# helmet_blinker_light_v0_2.net
KiCad netlist of a schematic drawn in EAGLE
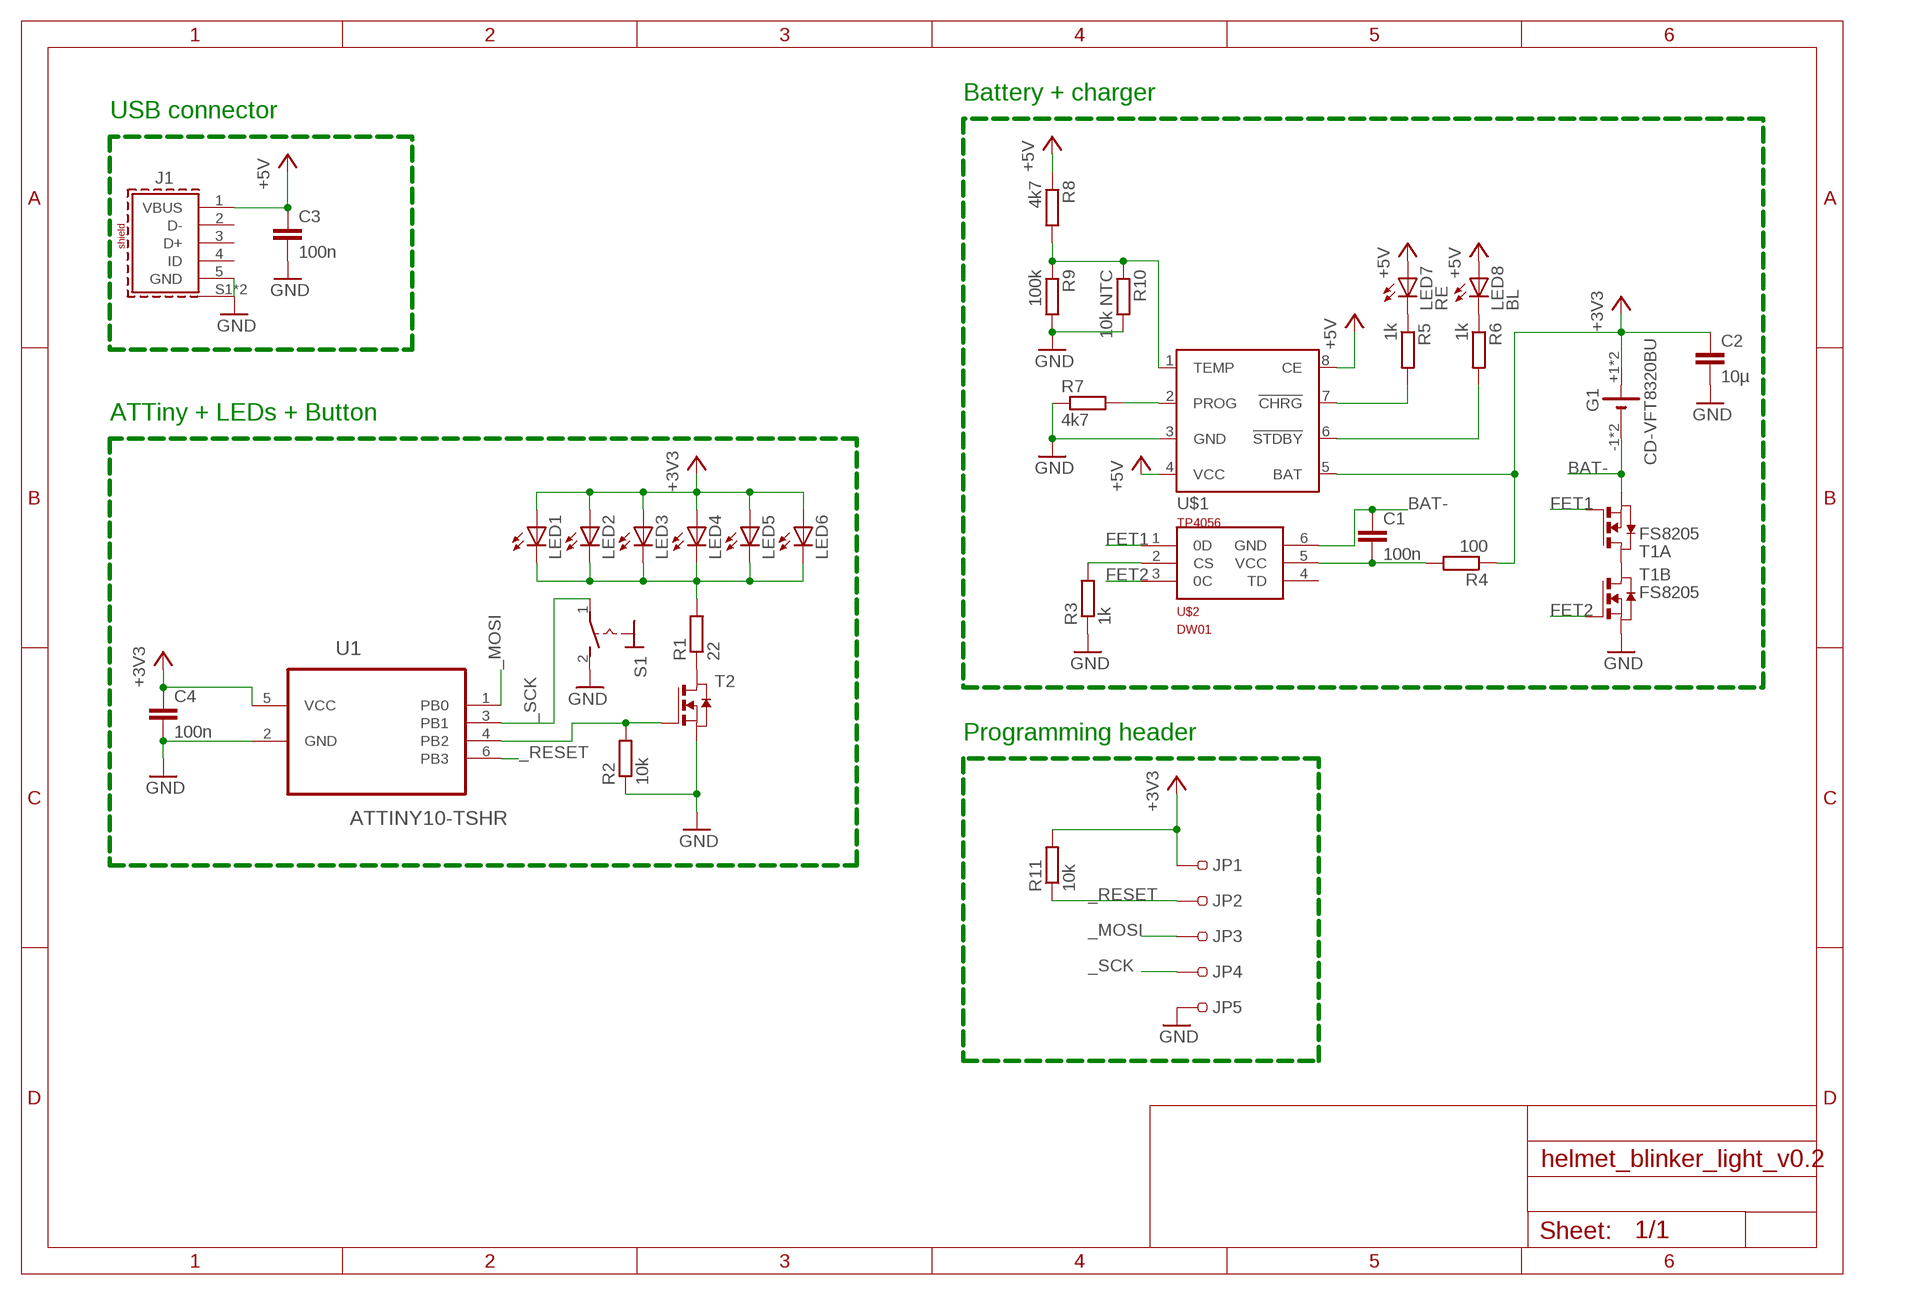
[diagram p0: schematic, sheet 1]

(export (version "E")
  (design (tool "Eeschema 10.0.6"))
  (components
    (comp (ref "C1")
      (value "100n")
      (footprint "eagle-import:C0402K")
      (libsource (lib "eagle-import") (part "C-EUC0402K"))
    )
    (comp (ref "C2")
      (value "10µ")
      (footprint "eagle-import:C0805K")
      (libsource (lib "eagle-import") (part "C-EUC0805K"))
    )
    (comp (ref "C3")
      (value "100n")
      (footprint "eagle-import:C0402K")
      (libsource (lib "eagle-import") (part "C-EUC0402K"))
    )
    (comp (ref "C4")
      (value "100n")
      (footprint "eagle-import:C0402K")
      (libsource (lib "eagle-import") (part "C-EUC0402K"))
    )
    (comp (ref "G1")
      (value "CD-VFT8320BU")
      (footprint "eagle-import:CS-VFT8320BU")
      (libsource (lib "eagle-import") (part "CD-VFT8320BU"))
    )
    (comp (ref "J1")
      (value "614105150621")
      (footprint "eagle-import:614105150621")
      (libsource (lib "eagle-import") (part "614105150621"))
    )
    (comp (ref "JP1")
      (value "0.7MM_POGO-PINS")
      (footprint "eagle-import:0.7MM_POGO-PINS")
      (libsource (lib "eagle-import") (part "0.7MM_POGO-PINS"))
    )
    (comp (ref "JP2")
      (value "0.7MM_POGO-PINS")
      (footprint "eagle-import:0.7MM_POGO-PINS")
      (libsource (lib "eagle-import") (part "0.7MM_POGO-PINS"))
    )
    (comp (ref "JP3")
      (value "0.7MM_POGO-PINS")
      (footprint "eagle-import:0.7MM_POGO-PINS")
      (libsource (lib "eagle-import") (part "0.7MM_POGO-PINS"))
    )
    (comp (ref "JP4")
      (value "0.7MM_POGO-PINS")
      (footprint "eagle-import:0.7MM_POGO-PINS")
      (libsource (lib "eagle-import") (part "0.7MM_POGO-PINS"))
    )
    (comp (ref "JP5")
      (value "0.7MM_POGO-PINS")
      (footprint "eagle-import:0.7MM_POGO-PINS")
      (libsource (lib "eagle-import") (part "0.7MM_POGO-PINS"))
    )
    (comp (ref "LED1")
      (value "LEDCHIPLED_0805")
      (footprint "eagle-import:CHIPLED_0805")
      (libsource (lib "eagle-import") (part "LEDCHIPLED_0805"))
    )
    (comp (ref "LED2")
      (value "LEDCHIPLED_0805")
      (footprint "eagle-import:CHIPLED_0805")
      (libsource (lib "eagle-import") (part "LEDCHIPLED_0805"))
    )
    (comp (ref "LED3")
      (value "LEDCHIPLED_0805")
      (footprint "eagle-import:CHIPLED_0805")
      (libsource (lib "eagle-import") (part "LEDCHIPLED_0805"))
    )
    (comp (ref "LED4")
      (value "LEDCHIPLED_0805")
      (footprint "eagle-import:CHIPLED_0805")
      (libsource (lib "eagle-import") (part "LEDCHIPLED_0805"))
    )
    (comp (ref "LED5")
      (value "LEDCHIPLED_0805")
      (footprint "eagle-import:CHIPLED_0805")
      (libsource (lib "eagle-import") (part "LEDCHIPLED_0805"))
    )
    (comp (ref "LED6")
      (value "LEDCHIPLED_0805")
      (footprint "eagle-import:CHIPLED_0805")
      (libsource (lib "eagle-import") (part "LEDCHIPLED_0805"))
    )
    (comp (ref "LED7")
      (value "RE")
      (footprint "eagle-import:CHIPLED_0805")
      (libsource (lib "eagle-import") (part "LEDCHIPLED_0805"))
    )
    (comp (ref "LED8")
      (value "BL")
      (footprint "eagle-import:CHIPLED_0805")
      (libsource (lib "eagle-import") (part "LEDCHIPLED_0805"))
    )
    (comp (ref "R1")
      (value "22")
      (footprint "eagle-import:R0805")
      (libsource (lib "eagle-import") (part "R-EU_R0805"))
    )
    (comp (ref "R2")
      (value "10k")
      (footprint "eagle-import:R0402")
      (libsource (lib "eagle-import") (part "R-EU_R0402"))
    )
    (comp (ref "R3")
      (value "1k")
      (footprint "eagle-import:R0402")
      (libsource (lib "eagle-import") (part "R-EU_R0402"))
    )
    (comp (ref "R4")
      (value "100")
      (footprint "eagle-import:R0402")
      (libsource (lib "eagle-import") (part "R-EU_R0402"))
    )
    (comp (ref "R5")
      (value "1k")
      (footprint "eagle-import:R0402")
      (libsource (lib "eagle-import") (part "R-EU_R0402"))
    )
    (comp (ref "R6")
      (value "1k")
      (footprint "eagle-import:R0402")
      (libsource (lib "eagle-import") (part "R-EU_R0402"))
    )
    (comp (ref "R7")
      (value "4k7")
      (footprint "eagle-import:R0402")
      (libsource (lib "eagle-import") (part "R-EU_R0402"))
    )
    (comp (ref "R8")
      (value "4k7")
      (footprint "eagle-import:R0402")
      (libsource (lib "eagle-import") (part "R-EU_R0402"))
    )
    (comp (ref "R9")
      (value "100k")
      (footprint "eagle-import:R0402")
      (libsource (lib "eagle-import") (part "R-EU_R0402"))
    )
    (comp (ref "R10")
      (value "10k NTC")
      (footprint "eagle-import:R0805")
      (libsource (lib "eagle-import") (part "R-EU_R0805"))
    )
    (comp (ref "R11")
      (value "10k")
      (footprint "eagle-import:R0402")
      (libsource (lib "eagle-import") (part "R-EU_R0402"))
    )
    (comp (ref "S1")
      (value "TS-1088")
      (footprint "eagle-import:TS-1088")
      (libsource (lib "eagle-import") (part "TS-1088"))
    )
    (comp (ref "T1")
      (value "FS8205")
      (footprint "eagle-import:TSSOP-8")
      (libsource (lib "eagle-import") (part "DMN3024LSD"))
    )
    (comp (ref "T2")
      (value "NMOSSOT23")
      (footprint "eagle-import:SOT-23")
      (libsource (lib "eagle-import") (part "NMOSSOT23"))
    )
    (comp (ref "U$1")
      (value "TP4056")
      (footprint "eagle-import:SOT23-8")
      (libsource (lib "eagle-import") (part "TP4056"))
    )
    (comp (ref "U$2")
      (value "DW01")
      (footprint "eagle-import:SOT23-6")
      (libsource (lib "eagle-import") (part "DW01"))
    )
    (comp (ref "U1")
      (value "ATTINY10-TSHR")
      (footprint "eagle-import:SOT95P280X145-6N")
      (libsource (lib "eagle-import") (part "ATTINY10-TSHR"))
    )
  )
  (nets
    (net (code "1") (name "+3V3") (class "Default")
      (node (ref "C2") (pin "1") (pinfunction "1_1") (pintype "passive"))
      (node (ref "C4") (pin "1") (pinfunction "1_1") (pintype "passive"))
      (node (ref "G1") (pin "+1") (pinfunction "+_+1") (pintype "passive"))
      (node (ref "G1") (pin "+2") (pinfunction "+_+2") (pintype "passive"))
      (node (ref "JP1") (pin "1") (pinfunction "1_1") (pintype "passive"))
      (node (ref "LED1") (pin "A") (pinfunction "A_A") (pintype "passive"))
      (node (ref "LED2") (pin "A") (pinfunction "A_A") (pintype "passive"))
      (node (ref "LED3") (pin "A") (pinfunction "A_A") (pintype "passive"))
      (node (ref "LED4") (pin "A") (pinfunction "A_A") (pintype "passive"))
      (node (ref "LED5") (pin "A") (pinfunction "A_A") (pintype "passive"))
      (node (ref "LED6") (pin "A") (pinfunction "A_A") (pintype "passive"))
      (node (ref "R11") (pin "2") (pinfunction "2_2") (pintype "passive"))
      (node (ref "R4") (pin "1") (pinfunction "1_1") (pintype "passive"))
      (node (ref "U$1") (pin "5") (pinfunction "BAT_5") (pintype "bidirectional"))
      (node (ref "U1") (pin "5") (pinfunction "VCC_5") (pintype "power_in"))
    )
    (net (code "2") (name "+5V") (class "Default")
      (node (ref "C3") (pin "1") (pinfunction "1_1") (pintype "passive"))
      (node (ref "J1") (pin "1") (pinfunction "VBUS_1") (pintype "passive"))
      (node (ref "LED7") (pin "A") (pinfunction "A_A") (pintype "passive"))
      (node (ref "LED8") (pin "A") (pinfunction "A_A") (pintype "passive"))
      (node (ref "R8") (pin "1") (pinfunction "1_1") (pintype "passive"))
      (node (ref "U$1") (pin "4") (pinfunction "VCC_4") (pintype "bidirectional"))
      (node (ref "U$1") (pin "8") (pinfunction "CE_8") (pintype "bidirectional"))
    )
    (net (code "3") (name "/BAT-") (class "Default")
      (node (ref "C1") (pin "1") (pinfunction "1_1") (pintype "passive"))
      (node (ref "G1") (pin "-1") (pinfunction "-_-1") (pintype "passive"))
      (node (ref "G1") (pin "-2") (pinfunction "-_-2") (pintype "passive"))
      (node (ref "T1") (pin "2") (pinfunction "S_2") (pintype "passive"))
      (node (ref "T1") (pin "3") (pinfunction "S_3") (pintype "passive"))
      (node (ref "U$2") (pin "6") (pinfunction "GND_6") (pintype "bidirectional"))
    )
    (net (code "4") (name "/FET1") (class "Default")
      (node (ref "T1") (pin "4") (pinfunction "G_4") (pintype "passive"))
      (node (ref "U$2") (pin "1") (pinfunction "0D_1") (pintype "bidirectional"))
    )
    (net (code "5") (name "/FET2") (class "Default")
      (node (ref "T1") (pin "5") (pinfunction "G_5") (pintype "passive"))
      (node (ref "U$2") (pin "3") (pinfunction "0C_3") (pintype "bidirectional"))
    )
    (net (code "6") (name "/_MOSI") (class "Default")
      (node (ref "JP3") (pin "1") (pinfunction "1_1") (pintype "passive"))
      (node (ref "U1") (pin "1") (pinfunction "PB0_1") (pintype "bidirectional"))
    )
    (net (code "7") (name "/_RESET") (class "Default")
      (node (ref "JP2") (pin "1") (pinfunction "1_1") (pintype "passive"))
      (node (ref "R11") (pin "1") (pinfunction "1_1") (pintype "passive"))
      (node (ref "U1") (pin "6") (pinfunction "PB3_6") (pintype "bidirectional"))
    )
    (net (code "8") (name "/_SCK") (class "Default")
      (node (ref "JP4") (pin "1") (pinfunction "1_1") (pintype "passive"))
      (node (ref "S1") (pin "1") (pinfunction "P_1") (pintype "passive"))
      (node (ref "U1") (pin "3") (pinfunction "PB1_3") (pintype "bidirectional"))
    )
    (net (code "9") (name "GND") (class "Default")
      (node (ref "C2") (pin "2") (pinfunction "2_2") (pintype "passive"))
      (node (ref "C3") (pin "2") (pinfunction "2_2") (pintype "passive"))
      (node (ref "C4") (pin "2") (pinfunction "2_2") (pintype "passive"))
      (node (ref "J1") (pin "5") (pinfunction "GND_5") (pintype "passive"))
      (node (ref "J1") (pin "S1") (pinfunction "SHIELD_S1") (pintype "passive"))
      (node (ref "J1") (pin "S2") (pinfunction "SHIELD_S2") (pintype "passive"))
      (node (ref "JP5") (pin "1") (pinfunction "1_1") (pintype "passive"))
      (node (ref "R10") (pin "2") (pinfunction "2_2") (pintype "passive"))
      (node (ref "R2") (pin "1") (pinfunction "1_1") (pintype "passive"))
      (node (ref "R3") (pin "1") (pinfunction "1_1") (pintype "passive"))
      (node (ref "R7") (pin "1") (pinfunction "1_1") (pintype "passive"))
      (node (ref "R9") (pin "2") (pinfunction "2_2") (pintype "passive"))
      (node (ref "S1") (pin "2") (pinfunction "S_2") (pintype "passive"))
      (node (ref "T1") (pin "6") (pinfunction "S_6") (pintype "passive"))
      (node (ref "T1") (pin "7") (pinfunction "S_7") (pintype "passive"))
      (node (ref "T2") (pin "2") (pinfunction "S_2") (pintype "passive"))
      (node (ref "U$1") (pin "3") (pinfunction "GND_3") (pintype "bidirectional"))
      (node (ref "U1") (pin "2") (pinfunction "GND_2") (pintype "passive"))
    )
    (net (code "10") (name "Net-(LED1-PadC)") (class "Default")
      (node (ref "LED1") (pin "C") (pinfunction "C_C") (pintype "passive"))
      (node (ref "LED2") (pin "C") (pinfunction "C_C") (pintype "passive"))
      (node (ref "LED3") (pin "C") (pinfunction "C_C") (pintype "passive"))
      (node (ref "LED4") (pin "C") (pinfunction "C_C") (pintype "passive"))
      (node (ref "LED5") (pin "C") (pinfunction "C_C") (pintype "passive"))
      (node (ref "LED6") (pin "C") (pinfunction "C_C") (pintype "passive"))
      (node (ref "R1") (pin "2") (pinfunction "2_2") (pintype "passive"))
    )
    (net (code "11") (name "Net-(LED7-PadC)") (class "Default")
      (node (ref "LED7") (pin "C") (pinfunction "C_C") (pintype "passive"))
      (node (ref "R5") (pin "1") (pinfunction "1_1") (pintype "passive"))
    )
    (net (code "12") (name "Net-(LED8-PadC)") (class "Default")
      (node (ref "LED8") (pin "C") (pinfunction "C_C") (pintype "passive"))
      (node (ref "R6") (pin "1") (pinfunction "1_1") (pintype "passive"))
    )
    (net (code "13") (name "Net-(T1A-D)") (class "Default")
      (node (ref "T1") (pin "1") (pinfunction "D_1") (pintype "passive"))
      (node (ref "T1") (pin "8") (pinfunction "D_8") (pintype "passive"))
    )
    (net (code "14") (name "Net-(T2-D)") (class "Default")
      (node (ref "R1") (pin "1") (pinfunction "1_1") (pintype "passive"))
      (node (ref "T2") (pin "1") (pinfunction "D_1") (pintype "passive"))
    )
    (net (code "15") (name "Net-(T2-G)") (class "Default")
      (node (ref "R2") (pin "2") (pinfunction "2_2") (pintype "passive"))
      (node (ref "T2") (pin "3") (pinfunction "G_3") (pintype "passive"))
      (node (ref "U1") (pin "4") (pinfunction "PB2_4") (pintype "bidirectional"))
    )
    (net (code "16") (name "Net-(U$1-PROG)") (class "Default")
      (node (ref "R7") (pin "2") (pinfunction "2_2") (pintype "passive"))
      (node (ref "U$1") (pin "2") (pinfunction "PROG_2") (pintype "bidirectional"))
    )
    (net (code "17") (name "Net-(U$1-TEMP)") (class "Default")
      (node (ref "R10") (pin "1") (pinfunction "1_1") (pintype "passive"))
      (node (ref "R8") (pin "2") (pinfunction "2_2") (pintype "passive"))
      (node (ref "R9") (pin "1") (pinfunction "1_1") (pintype "passive"))
      (node (ref "U$1") (pin "1") (pinfunction "TEMP_1") (pintype "bidirectional"))
    )
    (net (code "18") (name "Net-(U$1-~{CHRG})") (class "Default")
      (node (ref "R5") (pin "2") (pinfunction "2_2") (pintype "passive"))
      (node (ref "U$1") (pin "7") (pinfunction "~{CHRG}_7") (pintype "bidirectional"))
    )
    (net (code "19") (name "Net-(U$1-~{STDBY})") (class "Default")
      (node (ref "R6") (pin "2") (pinfunction "2_2") (pintype "passive"))
      (node (ref "U$1") (pin "6") (pinfunction "~{STDBY}_6") (pintype "bidirectional"))
    )
    (net (code "20") (name "Net-(U$2-CS)") (class "Default")
      (node (ref "R3") (pin "2") (pinfunction "2_2") (pintype "passive"))
      (node (ref "U$2") (pin "2") (pinfunction "CS_2") (pintype "bidirectional"))
    )
    (net (code "21") (name "Net-(U$2-VCC)") (class "Default")
      (node (ref "C1") (pin "2") (pinfunction "2_2") (pintype "passive"))
      (node (ref "R4") (pin "2") (pinfunction "2_2") (pintype "passive"))
      (node (ref "U$2") (pin "5") (pinfunction "VCC_5") (pintype "bidirectional"))
    )
    (net (code "22") (name "unconnected-(J1-D+-Pad3)") (class "Default")
      (node (ref "J1") (pin "3") (pinfunction "D+_3") (pintype "passive"))
    )
    (net (code "23") (name "unconnected-(J1-D--Pad2)") (class "Default")
      (node (ref "J1") (pin "2") (pinfunction "D-_2") (pintype "passive"))
    )
    (net (code "24") (name "unconnected-(J1-ID-Pad4)") (class "Default")
      (node (ref "J1") (pin "4") (pinfunction "ID_4") (pintype "passive"))
    )
    (net (code "25") (name "unconnected-(U$2-TD-Pad4)") (class "Default")
      (node (ref "U$2") (pin "4") (pinfunction "TD_4") (pintype "bidirectional"))
    )
  )
)
